# 1ssrCompactBoard.net
KiCad netlist of a schematic drawn in EAGLE
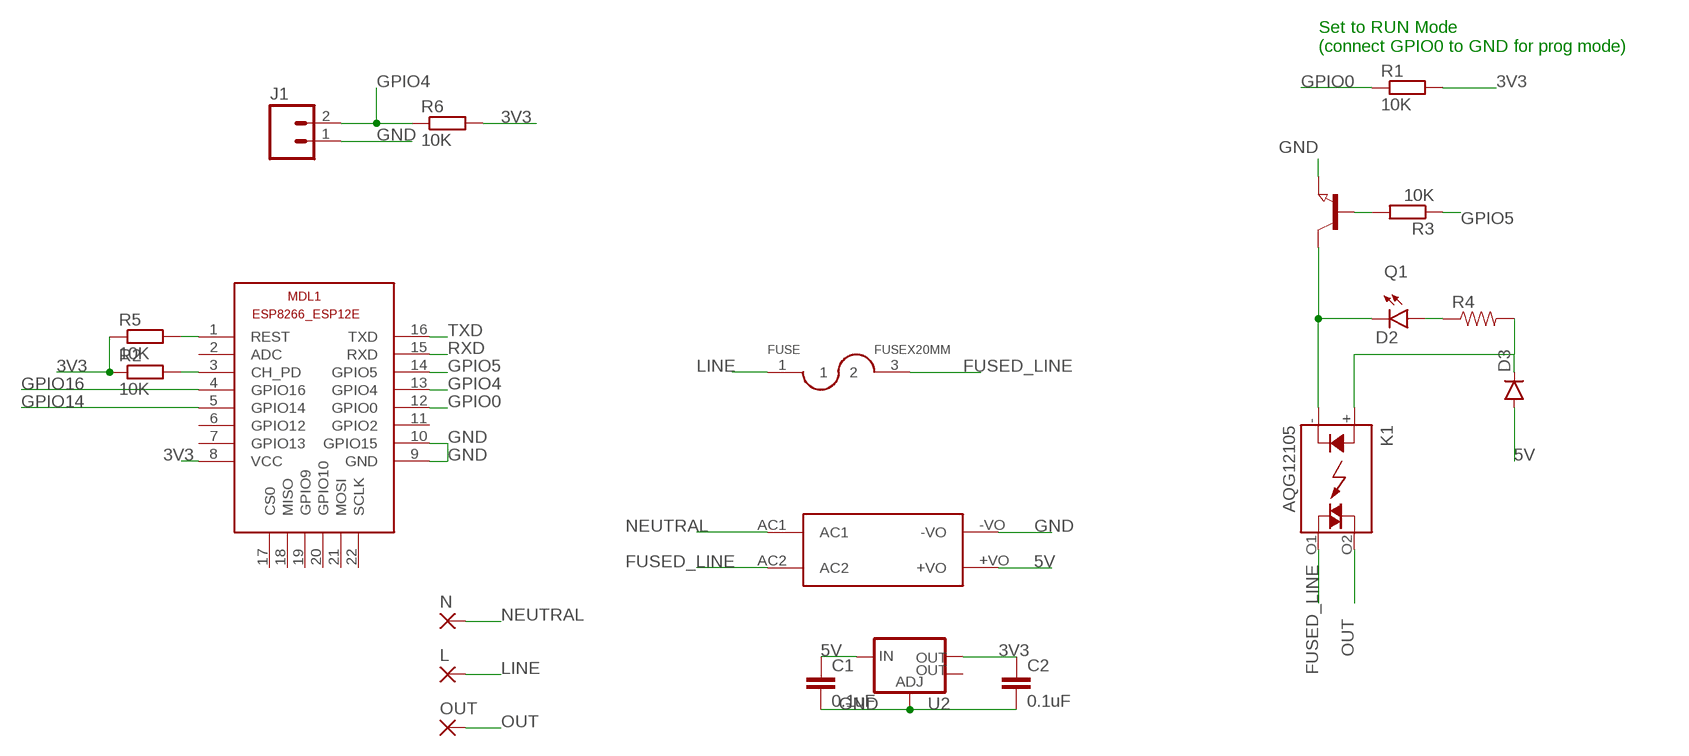
[diagram p0: schematic, sheet 1]

(export (version "E")
  (design (tool "Eeschema 10.0.6"))
  (components
    (comp (ref "C1")
      (value "0.1uF")
      (footprint "eagle-import:0603-CAP")
      (libsource (lib "eagle-import") (part "0.1UF-25V-5%(0603)"))
    )
    (comp (ref "C2")
      (value "0.1uF")
      (footprint "eagle-import:0603-CAP")
      (libsource (lib "eagle-import") (part "0.1UF-25V-5%(0603)"))
    )
    (comp (ref "D2")
      (value "LED0603")
      (footprint "eagle-import:LED-0603")
      (libsource (lib "eagle-import") (part "LED0603"))
    )
    (comp (ref "D3")
      (value "DIODESMA")
      (footprint "eagle-import:SMA-DIODE")
      (libsource (lib "eagle-import") (part "DIODESMA"))
    )
    (comp (ref "FUSE")
      (value "FUSEX20MM")
      (footprint "eagle-import:FUSE_5MM")
      (libsource (lib "eagle-import") (part "FUSEX20MM"))
    )
    (comp (ref "J1")
      (value "M02PTH3")
      (footprint "eagle-import:1X02_LONGPADS")
      (libsource (lib "eagle-import") (part "M02PTH3"))
    )
    (comp (ref "K1")
      (value "AQG12105")
      (footprint "eagle-import:AQG")
      (fields (field (name "MF") "AROMAT/ MATSUSHITA"))
      (libsource (lib "eagle-import") (part "AQG12105"))
    )
    (comp (ref "L")
      (value "3,81/1,1")
      (footprint "eagle-import:3,81_1,1")
      (libsource (lib "eagle-import") (part "3,81/1,1"))
    )
    (comp (ref "MDL1")
      (value "ESP8266-12EESP8266-ESP12E")
      (footprint "eagle-import:ESP8266-ESP12E")
      (libsource (lib "eagle-import") (part "ESP8266-12EESP8266-ESP12E"))
    )
    (comp (ref "N")
      (value "3,81/1,1")
      (footprint "eagle-import:3,81_1,1")
      (libsource (lib "eagle-import") (part "3,81/1,1"))
    )
    (comp (ref "OUT")
      (value "3,81/1,1")
      (footprint "eagle-import:3,81_1,1")
      (libsource (lib "eagle-import") (part "3,81/1,1"))
    )
    (comp (ref "Q1")
      (value "NPN-TRANSISTOR_SOT23")
      (footprint "eagle-import:SOT23")
      (libsource (lib "eagle-import") (part "NPN-TRANSISTOR_SOT23"))
    )
    (comp (ref "R1")
      (value "10K")
      (footprint "eagle-import:R0805")
      (libsource (lib "eagle-import") (part "R-EU_R0805"))
    )
    (comp (ref "R2")
      (value "10K")
      (footprint "eagle-import:R0805")
      (libsource (lib "eagle-import") (part "R-EU_R0805"))
    )
    (comp (ref "R3")
      (value "10K")
      (footprint "eagle-import:R0805")
      (libsource (lib "eagle-import") (part "R-EU_R0805"))
    )
    (comp (ref "R4")
      (value "RESISTOR0603")
      (footprint "eagle-import:0603-RES")
      (libsource (lib "eagle-import") (part "RESISTOR0603"))
    )
    (comp (ref "R5")
      (value "10K")
      (footprint "eagle-import:R0805")
      (libsource (lib "eagle-import") (part "R-EU_R0805"))
    )
    (comp (ref "R6")
      (value "10K")
      (footprint "eagle-import:R0805")
      (libsource (lib "eagle-import") (part "R-EU_R0805"))
    )
    (comp (ref "U$4")
      (value "HLK-PM01")
      (footprint "eagle-import:HLK-PM01")
      (libsource (lib "eagle-import") (part "HLK-PM01"))
    )
    (comp (ref "U2")
      (value "V_REG_LM1117SOT223")
      (footprint "eagle-import:SOT223")
      (libsource (lib "eagle-import") (part "V_REG_LM1117SOT223"))
    )
  )
  (nets
    (net (code "1") (name "/3V3") (class "Default")
      (node (ref "C2") (pin "1") (pinfunction "1_1") (pintype "passive"))
      (node (ref "MDL1") (pin "8") (pinfunction "VCC_8") (pintype "bidirectional"))
      (node (ref "R1") (pin "2") (pinfunction "2_2") (pintype "passive"))
      (node (ref "R2") (pin "1") (pinfunction "1_1") (pintype "passive"))
      (node (ref "R5") (pin "1") (pinfunction "1_1") (pintype "passive"))
      (node (ref "R6") (pin "2") (pinfunction "2_2") (pintype "passive"))
      (node (ref "U2") (pin "2") (pinfunction "OUT_2") (pintype "output"))
    )
    (net (code "2") (name "/5V") (class "Default")
      (node (ref "C1") (pin "1") (pinfunction "1_1") (pintype "passive"))
      (node (ref "D3") (pin "A") (pinfunction "A_A") (pintype "passive"))
      (node (ref "U$4") (pin "+VO") (pinfunction "+VO_+VO") (pintype "bidirectional"))
      (node (ref "U2") (pin "3") (pinfunction "IN_3") (pintype "input"))
    )
    (net (code "3") (name "/FUSED_LINE") (class "Default")
      (node (ref "FUSE") (pin "3") (pinfunction "2_3") (pintype "bidirectional"))
      (node (ref "K1") (pin "O1") (pinfunction "DS2_O1") (pintype "passive"))
      (node (ref "U$4") (pin "AC2") (pinfunction "AC2_AC2") (pintype "bidirectional"))
    )
    (net (code "4") (name "/GND") (class "Default")
      (node (ref "C1") (pin "2") (pinfunction "2_2") (pintype "passive"))
      (node (ref "C2") (pin "2") (pinfunction "2_2") (pintype "passive"))
      (node (ref "J1") (pin "1") (pinfunction "1_1") (pintype "passive"))
      (node (ref "MDL1") (pin "10") (pinfunction "GPIO15_10") (pintype "bidirectional"))
      (node (ref "MDL1") (pin "9") (pinfunction "GND_9") (pintype "bidirectional"))
      (node (ref "Q1") (pin "2") (pinfunction "E_2") (pintype "passive"))
      (node (ref "U$4") (pin "-VO") (pinfunction "-VO_-VO") (pintype "bidirectional"))
      (node (ref "U2") (pin "1") (pinfunction "ADJ_1") (pintype "input"))
    )
    (net (code "5") (name "/GPIO0") (class "Default")
      (node (ref "MDL1") (pin "12") (pinfunction "GPIO0_12") (pintype "bidirectional"))
      (node (ref "R1") (pin "1") (pinfunction "1_1") (pintype "passive"))
    )
    (net (code "6") (name "/GPIO4") (class "Default")
      (node (ref "J1") (pin "2") (pinfunction "2_2") (pintype "passive"))
      (node (ref "MDL1") (pin "13") (pinfunction "GPIO4_13") (pintype "bidirectional"))
      (node (ref "R6") (pin "1") (pinfunction "1_1") (pintype "passive"))
    )
    (net (code "7") (name "/GPIO5") (class "Default")
      (node (ref "MDL1") (pin "14") (pinfunction "GPIO5_14") (pintype "bidirectional"))
      (node (ref "R3") (pin "1") (pinfunction "1_1") (pintype "passive"))
    )
    (net (code "8") (name "/GPIO14") (class "Default")
      (node (ref "MDL1") (pin "5") (pinfunction "GPIO14_5") (pintype "bidirectional"))
    )
    (net (code "9") (name "/GPIO16") (class "Default")
      (node (ref "MDL1") (pin "4") (pinfunction "GPIO16_4") (pintype "bidirectional"))
    )
    (net (code "10") (name "/LINE") (class "Default")
      (node (ref "FUSE") (pin "1") (pinfunction "1_1") (pintype "bidirectional"))
      (node (ref "L") (pin "1") (pinfunction "P_1") (pintype "passive"))
    )
    (net (code "11") (name "/NEUTRAL") (class "Default")
      (node (ref "N") (pin "1") (pinfunction "P_1") (pintype "passive"))
      (node (ref "U$4") (pin "AC1") (pinfunction "AC1_AC1") (pintype "bidirectional"))
    )
    (net (code "12") (name "/OUT") (class "Default")
      (node (ref "K1") (pin "O2") (pinfunction "DS1_O2") (pintype "passive"))
      (node (ref "OUT") (pin "1") (pinfunction "P_1") (pintype "passive"))
    )
    (net (code "13") (name "/RXD") (class "Default")
      (node (ref "MDL1") (pin "15") (pinfunction "RXD_15") (pintype "bidirectional"))
    )
    (net (code "14") (name "/TXD") (class "Default")
      (node (ref "MDL1") (pin "16") (pinfunction "TXD_16") (pintype "bidirectional"))
    )
    (net (code "15") (name "Net-(D2-PadA)") (class "Default")
      (node (ref "D2") (pin "A") (pinfunction "A_A") (pintype "passive"))
      (node (ref "R4") (pin "1") (pinfunction "1_1") (pintype "passive"))
    )
    (net (code "16") (name "Net-(K1-A)") (class "Default")
      (node (ref "D3") (pin "C") (pinfunction "C_C") (pintype "passive"))
      (node (ref "K1") (pin "+") (pinfunction "A_+") (pintype "passive"))
      (node (ref "R4") (pin "2") (pinfunction "2_2") (pintype "passive"))
    )
    (net (code "17") (name "Net-(K1-K)") (class "Default")
      (node (ref "D2") (pin "C") (pinfunction "C_C") (pintype "passive"))
      (node (ref "K1") (pin "-") (pinfunction "K_-") (pintype "passive"))
      (node (ref "Q1") (pin "3") (pinfunction "C_3") (pintype "passive"))
    )
    (net (code "18") (name "Net-(MDL1-CH_PD)") (class "Default")
      (node (ref "MDL1") (pin "3") (pinfunction "CH_PD_3") (pintype "bidirectional"))
      (node (ref "R2") (pin "2") (pinfunction "2_2") (pintype "passive"))
    )
    (net (code "19") (name "Net-(MDL1-REST)") (class "Default")
      (node (ref "MDL1") (pin "1") (pinfunction "REST_1") (pintype "bidirectional"))
      (node (ref "R5") (pin "2") (pinfunction "2_2") (pintype "passive"))
    )
    (net (code "20") (name "Net-(Q1-B)") (class "Default")
      (node (ref "Q1") (pin "1") (pinfunction "B_1") (pintype "passive"))
      (node (ref "R3") (pin "2") (pinfunction "2_2") (pintype "passive"))
    )
    (net (code "21") (name "unconnected-(MDL1-ADC-Pad2)") (class "Default")
      (node (ref "MDL1") (pin "2") (pinfunction "ADC_2") (pintype "bidirectional"))
    )
    (net (code "22") (name "unconnected-(MDL1-CS0-Pad17)") (class "Default")
      (node (ref "MDL1") (pin "17") (pinfunction "CS0_17") (pintype "bidirectional"))
    )
    (net (code "23") (name "unconnected-(MDL1-GPIO2-Pad11)") (class "Default")
      (node (ref "MDL1") (pin "11") (pinfunction "GPIO2_11") (pintype "bidirectional"))
    )
    (net (code "24") (name "unconnected-(MDL1-GPIO9-Pad19)") (class "Default")
      (node (ref "MDL1") (pin "19") (pinfunction "GPIO9_19") (pintype "bidirectional"))
    )
    (net (code "25") (name "unconnected-(MDL1-GPIO10-Pad20)") (class "Default")
      (node (ref "MDL1") (pin "20") (pinfunction "GPIO10_20") (pintype "bidirectional"))
    )
    (net (code "26") (name "unconnected-(MDL1-GPIO12-Pad6)") (class "Default")
      (node (ref "MDL1") (pin "6") (pinfunction "GPIO12_6") (pintype "bidirectional"))
    )
    (net (code "27") (name "unconnected-(MDL1-GPIO13-Pad7)") (class "Default")
      (node (ref "MDL1") (pin "7") (pinfunction "GPIO13_7") (pintype "bidirectional"))
    )
    (net (code "28") (name "unconnected-(MDL1-MISO-Pad18)") (class "Default")
      (node (ref "MDL1") (pin "18") (pinfunction "MISO_18") (pintype "bidirectional"))
    )
    (net (code "29") (name "unconnected-(MDL1-MOSI-Pad21)") (class "Default")
      (node (ref "MDL1") (pin "21") (pinfunction "MOSI_21") (pintype "bidirectional"))
    )
    (net (code "30") (name "unconnected-(MDL1-SCLK-Pad22)") (class "Default")
      (node (ref "MDL1") (pin "22") (pinfunction "SCLK_22") (pintype "bidirectional"))
    )
    (net (code "31") (name "unconnected-(U2-OUT-Pad4)") (class "Default")
      (node (ref "U2") (pin "4") (pinfunction "OUT_4") (pintype "output"))
    )
  )
)
